# STM32F407.net
KiCad netlist of a schematic drawn in Altium Designer
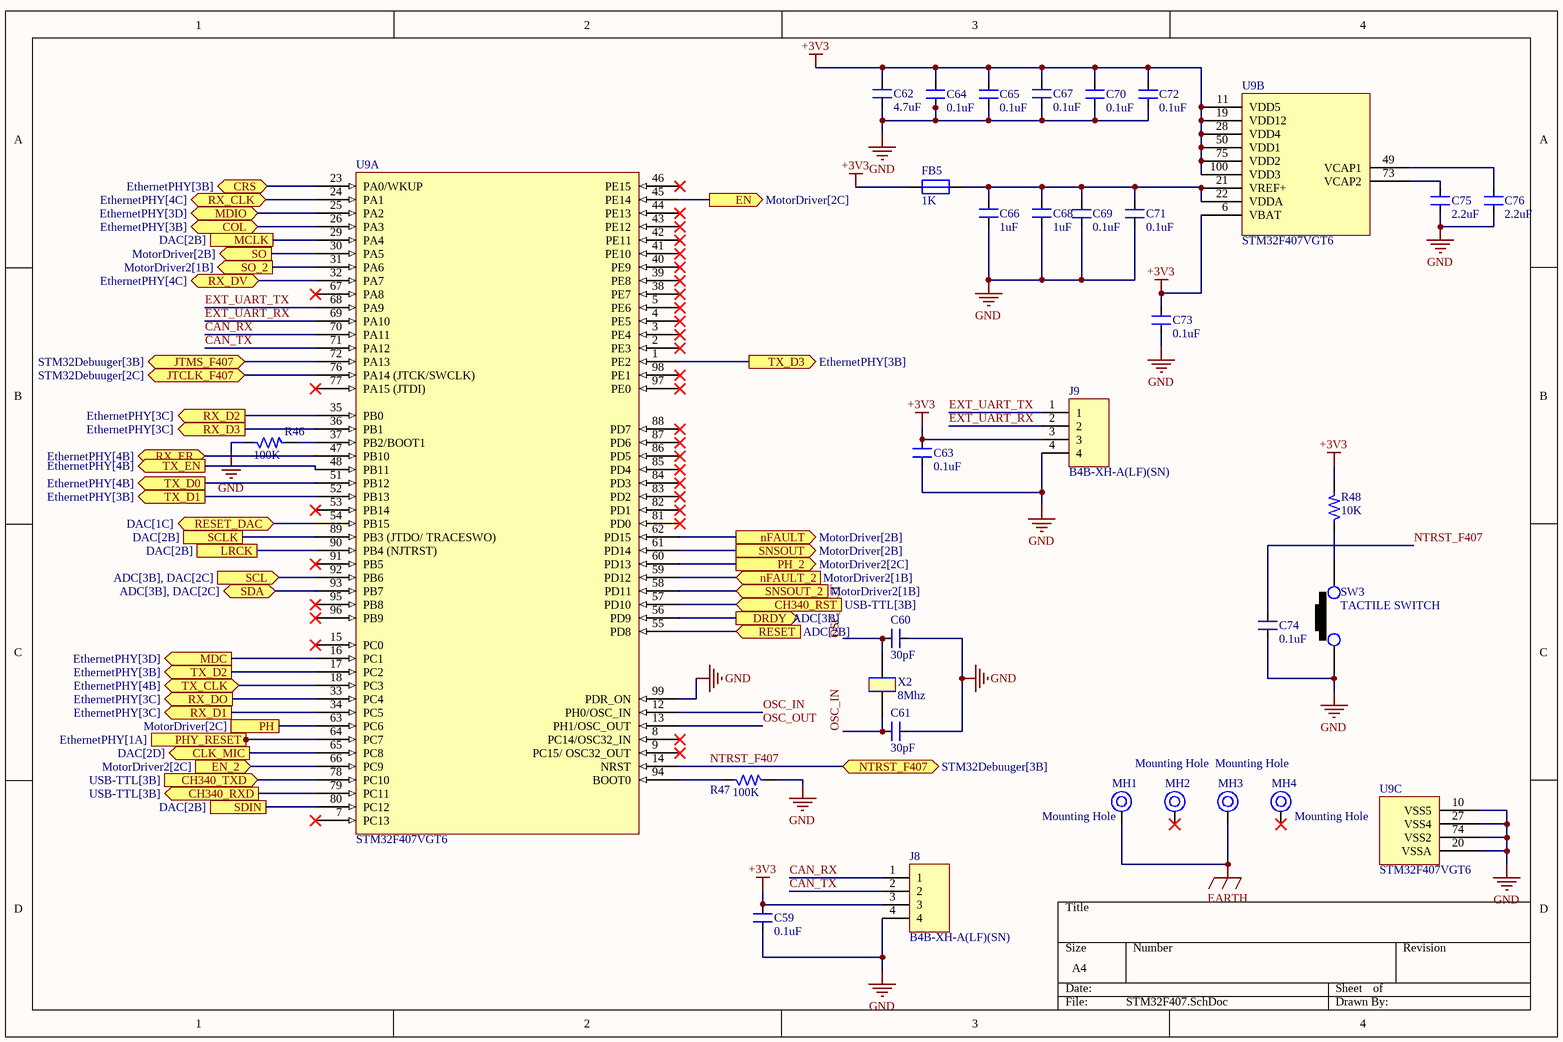
[diagram p0: STM32F407.SchDoc]

(export (version "E")
  (design (tool "Eeschema 10.0.6"))
  (components
    (comp (ref "C59")
      (value "0.1uF")
      (footprint "CAP_0805")
      (description "0.1µF ±10% 50V Ceramic Capacitor X7R 0805 (2012 Metric)")
      (fields
        (field (name "MANUFACTURER") "Samsung")
        (field (name "MANUFACTURER PART NUMBER") "CL21B104KBCNNNC")
      )
      (libsource (lib "ESTEEMPCBLIB") (part "CAP_0.1uF-50V-10%-0805"))
    )
    (comp (ref "C60")
      (value "30pF")
      (footprint "CAP_0805")
      (description "±10% 50V Ceramic Capacitor C0G, NP0 0805 (2012 Metric)")
      (fields
        (field (name "MANUFACTURER PART NUMBER") "C0805C300K5GAC7800")
        (field (name "MANUFACTURER") "KEMET")
      )
      (libsource (lib "ESTEEMPCBLIB") (part "CAP_30pF-50V-10%-0805"))
    )
    (comp (ref "C61")
      (value "30pF")
      (footprint "CAP_0805")
      (description "±10% 50V Ceramic Capacitor C0G, NP0 0805 (2012 Metric)")
      (fields
        (field (name "MANUFACTURER PART NUMBER") "C0805C300K5GAC7800")
        (field (name "MANUFACTURER") "KEMET")
      )
      (libsource (lib "ESTEEMPCBLIB") (part "CAP_30pF-50V-10%-0805"))
    )
    (comp (ref "C62")
      (value "4.7uF")
      (footprint "CAP_0805")
      (description "4.7µF ±10% 50V Ceramic Capacitor X5R 0805 (2012 Metric)")
      (fields
        (field (name "MANUFACTURER") "Yageo")
        (field (name "MANUFACTURER PART NUMBER") "GRM21BR61H475KE51L")
      )
      (libsource (lib "ESTEEMPCBLIB") (part "CAP_4.7uF-50V-10%-0805"))
    )
    (comp (ref "C63")
      (value "0.1uF")
      (footprint "CAP_0805")
      (description "0.1µF ±10% 50V Ceramic Capacitor X7R 0805 (2012 Metric)")
      (fields
        (field (name "MANUFACTURER") "Samsung")
        (field (name "MANUFACTURER PART NUMBER") "CL21B104KBCNNNC")
      )
      (libsource (lib "ESTEEMPCBLIB") (part "CAP_0.1uF-50V-10%-0805"))
    )
    (comp (ref "C64")
      (value "0.1uF")
      (footprint "CAP_0805")
      (description "0.1µF ±10% 50V Ceramic Capacitor X7R 0805 (2012 Metric)")
      (fields
        (field (name "MANUFACTURER") "Samsung")
        (field (name "MANUFACTURER PART NUMBER") "CL21B104KBCNNNC")
      )
      (libsource (lib "ESTEEMPCBLIB") (part "CAP_0.1uF-50V-10%-0805"))
    )
    (comp (ref "C65")
      (value "0.1uF")
      (footprint "CAP_0805")
      (description "0.1µF ±10% 50V Ceramic Capacitor X7R 0805 (2012 Metric)")
      (fields
        (field (name "MANUFACTURER") "Samsung")
        (field (name "MANUFACTURER PART NUMBER") "CL21B104KBCNNNC")
      )
      (libsource (lib "ESTEEMPCBLIB") (part "CAP_0.1uF-50V-10%-0805"))
    )
    (comp (ref "C66")
      (value "1uF")
      (footprint "CAP_0805")
      (description "1µF ±5% 50V Ceramic Capacitor X7R 0805 (2012 Metric)")
      (fields
        (field (name "MANUFACTURER") "Samsung")
        (field (name "MANUFACTURER PART NUMBER") "CC0805JKX7R9BB105")
      )
      (libsource (lib "ESTEEMPCBLIB") (part "CAP_1uF-50V-5%-0805"))
    )
    (comp (ref "C67")
      (value "0.1uF")
      (footprint "CAP_0805")
      (description "0.1µF ±10% 50V Ceramic Capacitor X7R 0805 (2012 Metric)")
      (fields
        (field (name "MANUFACTURER") "Samsung")
        (field (name "MANUFACTURER PART NUMBER") "CL21B104KBCNNNC")
      )
      (libsource (lib "ESTEEMPCBLIB") (part "CAP_0.1uF-50V-10%-0805"))
    )
    (comp (ref "C68")
      (value "1uF")
      (footprint "CAP_0805")
      (description "1µF ±5% 50V Ceramic Capacitor X7R 0805 (2012 Metric)")
      (fields
        (field (name "MANUFACTURER") "Samsung")
        (field (name "MANUFACTURER PART NUMBER") "CC0805JKX7R9BB105")
      )
      (libsource (lib "ESTEEMPCBLIB") (part "CAP_1uF-50V-5%-0805"))
    )
    (comp (ref "C69")
      (value "0.1uF")
      (footprint "CAP_0805")
      (description "0.1µF ±10% 50V Ceramic Capacitor X7R 0805 (2012 Metric)")
      (fields
        (field (name "MANUFACTURER") "Samsung")
        (field (name "MANUFACTURER PART NUMBER") "CL21B104KBCNNNC")
      )
      (libsource (lib "ESTEEMPCBLIB") (part "CAP_0.1uF-50V-10%-0805"))
    )
    (comp (ref "C70")
      (value "0.1uF")
      (footprint "CAP_0805")
      (description "0.1µF ±10% 50V Ceramic Capacitor X7R 0805 (2012 Metric)")
      (fields
        (field (name "MANUFACTURER") "Samsung")
        (field (name "MANUFACTURER PART NUMBER") "CL21B104KBCNNNC")
      )
      (libsource (lib "ESTEEMPCBLIB") (part "CAP_0.1uF-50V-10%-0805"))
    )
    (comp (ref "C71")
      (value "0.1uF")
      (footprint "CAP_0805")
      (description "0.1µF ±10% 50V Ceramic Capacitor X7R 0805 (2012 Metric)")
      (fields
        (field (name "MANUFACTURER") "Samsung")
        (field (name "MANUFACTURER PART NUMBER") "CL21B104KBCNNNC")
      )
      (libsource (lib "ESTEEMPCBLIB") (part "CAP_0.1uF-50V-10%-0805"))
    )
    (comp (ref "C72")
      (value "0.1uF")
      (footprint "CAP_0805")
      (description "0.1µF ±10% 50V Ceramic Capacitor X7R 0805 (2012 Metric)")
      (fields
        (field (name "MANUFACTURER") "Samsung")
        (field (name "MANUFACTURER PART NUMBER") "CL21B104KBCNNNC")
      )
      (libsource (lib "ESTEEMPCBLIB") (part "CAP_0.1uF-50V-10%-0805"))
    )
    (comp (ref "C73")
      (value "0.1uF")
      (footprint "CAP_0805")
      (description "0.1µF ±10% 50V Ceramic Capacitor X7R 0805 (2012 Metric)")
      (fields
        (field (name "MANUFACTURER") "Samsung")
        (field (name "MANUFACTURER PART NUMBER") "CL21B104KBCNNNC")
      )
      (libsource (lib "ESTEEMPCBLIB") (part "CAP_0.1uF-50V-10%-0805"))
    )
    (comp (ref "C74")
      (value "0.1uF")
      (footprint "CAP_0805")
      (description "0.1µF ±10% 50V Ceramic Capacitor X7R 0805 (2012 Metric)")
      (fields
        (field (name "MANUFACTURER") "Samsung")
        (field (name "MANUFACTURER PART NUMBER") "CL21B104KBCNNNC")
      )
      (libsource (lib "ESTEEMPCBLIB") (part "CAP_0.1uF-50V-10%-0805"))
    )
    (comp (ref "C75")
      (value "2.2uF")
      (footprint "CAP_0805")
      (description "2.2µF ±10% 25V Ceramic Capacitor X7R 0805 (2012 Metric)")
      (fields
        (field (name "MANUFACTURER") "KEMET")
        (field (name "MANUFACTURER PART NUMBER") "CL21B225KAFNFNE")
      )
      (libsource (lib "ESTEEMPCBLIB") (part "CAP_2.2uF-25V-10%-0805"))
    )
    (comp (ref "C76")
      (value "2.2uF")
      (footprint "CAP_0805")
      (description "2.2µF ±10% 25V Ceramic Capacitor X7R 0805 (2012 Metric)")
      (fields
        (field (name "MANUFACTURER") "KEMET")
        (field (name "MANUFACTURER PART NUMBER") "CL21B225KAFNFNE")
      )
      (libsource (lib "ESTEEMPCBLIB") (part "CAP_2.2uF-25V-10%-0805"))
    )
    (comp (ref "FB5")
      (value "1K")
      (footprint "IND_0805")
      (description "1 kOhms @ 100MHz 1 Power Line Ferrite Bead 0805 (2012 Metric) 1.6A")
      (fields
        (field (name "MANUFACTURER") "Laird")
        (field (name "MANUFACTURER PART NUMBER") "BLM21SP102SH1D")
      )
      (libsource (lib "ESTEEMPCBLIB") (part "FB_1K-100MHZ-1.6A-0805"))
    )
    (comp (ref "J8")
      (value "B4B-XH-A(LF)(SN)")
      (footprint "CON4_100_B4B-XH-A_TH_ST")
      (description "4 Pins, 1 Row 2.54mm Pitch, straight Connector, male")
      (fields (field (name "MANUFACTURER") "Wurth Electronics") (field (name "MATING PART NUMBER") "XHP-4"))
      (libsource (lib "ESTEEMPCBLIB") (part "CON-PLG_4X1-100-ST-TH"))
    )
    (comp (ref "J9")
      (value "B4B-XH-A(LF)(SN)")
      (footprint "CON4_100_B4B-XH-A_TH_ST")
      (description "4 Pins, 1 Row 2.54mm Pitch, straight Connector, male")
      (fields (field (name "MANUFACTURER") "Wurth Electronics") (field (name "MATING PART NUMBER") "XHP-4"))
      (libsource (lib "ESTEEMPCBLIB") (part "CON-PLG_4X1-100-ST-TH"))
    )
    (comp (ref "MH1")
      (value "Mounting Hole")
      (footprint "MOUNTING")
      (fields (field (name "MANUFACTURER PART NUMBER") "NA"))
      (libsource (lib "ESTEEMPCBLIB") (part "MH_3.5H_6D"))
    )
    (comp (ref "MH2")
      (value "Mounting Hole")
      (footprint "MOUNTING")
      (fields (field (name "MANUFACTURER PART NUMBER") "NA"))
      (libsource (lib "ESTEEMPCBLIB") (part "MH_3.5H_6D"))
    )
    (comp (ref "MH3")
      (value "Mounting Hole")
      (footprint "MOUNTING")
      (fields (field (name "MANUFACTURER PART NUMBER") "NA"))
      (libsource (lib "ESTEEMPCBLIB") (part "MH_3.5H_6D"))
    )
    (comp (ref "MH4")
      (value "Mounting Hole")
      (footprint "MOUNTING")
      (fields (field (name "MANUFACTURER PART NUMBER") "NA"))
      (libsource (lib "ESTEEMPCBLIB") (part "MH_3.5H_6D"))
    )
    (comp (ref "R46")
      (value "100K")
      (footprint "RES_0603")
      (description "100 kOhms ±1% 0.1W, 1/10W Chip Resistor 0603 (1608 Metric) Automotive AEC-Q200 Thick Film")
      (fields
        (field (name "MANUFACTURER") "Stackpole Electronics")
        (field (name "MANUFACTURER PART NUMBER") "RMCF0603FT100K")
      )
      (libsource (lib "ESTEEMPCBLIB") (part "RES_100K-0.1W-1%-0603"))
    )
    (comp (ref "R47")
      (value "100K")
      (footprint "RES_0603")
      (description "100 kOhms ±1% 0.1W, 1/10W Chip Resistor 0603 (1608 Metric) Automotive AEC-Q200 Thick Film")
      (fields
        (field (name "MANUFACTURER") "Stackpole Electronics")
        (field (name "MANUFACTURER PART NUMBER") "RMCF0603FT100K")
      )
      (libsource (lib "ESTEEMPCBLIB") (part "RES_100K-0.1W-1%-0603"))
    )
    (comp (ref "R48")
      (value "10K")
      (footprint "RES_0603")
      (description "10 kOhms ±1% 0.1W, 1/10W Chip Resistor 0603 (1608 Metric) Automotive AEC-Q200 Thick Film")
      (fields (field (name "MANUFACTURER") "Walsin") (field (name "MANUFACTURER PART NUMBER") "WR06X1002FTL"))
      (libsource (lib "ESTEEMPCBLIB") (part "RES_10K-0.1W-1%-0603"))
    )
    (comp (ref "SW3")
      (value "TACTILE SWITCH")
      (footprint "SW_342_SMD")
      (description "Tactile Switch SPST-NO Top Actuated Surface Mount")
      (fields
        (field (name "MANUFACTURER") "ITT C&K")
        (field (name "MANUFACTURER PART NUMBER") "RS-282G05A3-SMRT")
      )
      (libsource (lib "ESTEEMPCBLIB") (part "SW1_RS-282G05A3-SMRT-SMD"))
    )
    (comp (ref "U9")
      (value "STM32F407VGT6")
      (footprint "QFN100_19.6_669_58X10_SMD")
      (description "ARM® Cortex®-M4 STM32F4 Microcontroller IC 32-Bit 168MHz 1MB (1M x 8) FLASH 100-LQFP (14x14)")
      (fields (field (name "MANUFACTURER") "STMicroelectronics"))
      (libsource (lib "ESTEEMPCBLIB") (part "IC_STM32F407VGT6"))
    )
    (comp (ref "X2")
      (value "8Mhz")
      (footprint "XTAL_314_240X47_SMD")
      (description "8MHz ±30ppm Crystal 32pF 60 Ohms HC-49/US")
      (fields
        (field (name "MANUFACTURER") "Fox Electronics")
        (field (name "MANUFACTURER PART NUMBER") "ECS-80-32-5PX-TR")
      )
      (libsource (lib "ESTEEMPCBLIB") (part "XTAL_8MHZ-ECS-80-32-5PX-SMD"))
    )
  )
  (nets
    (net (code "1") (name "+3V3") (class "Default")
      (node (ref "C59") (pin "2") (pinfunction "2_2") (pintype "passive"))
      (node (ref "C62") (pin "2") (pinfunction "2_2") (pintype "passive"))
      (node (ref "C63") (pin "2") (pinfunction "2_2") (pintype "passive"))
      (node (ref "C64") (pin "2") (pinfunction "2_2") (pintype "passive"))
      (node (ref "C65") (pin "2") (pinfunction "2_2") (pintype "passive"))
      (node (ref "C67") (pin "2") (pinfunction "2_2") (pintype "passive"))
      (node (ref "C70") (pin "2") (pinfunction "2_2") (pintype "passive"))
      (node (ref "C72") (pin "2") (pinfunction "2_2") (pintype "passive"))
      (node (ref "C73") (pin "2") (pinfunction "2_2") (pintype "passive"))
      (node (ref "FB5") (pin "1") (pinfunction "1_1") (pintype "passive"))
      (node (ref "J8") (pin "3") (pinfunction "3_3") (pintype "passive"))
      (node (ref "J9") (pin "3") (pinfunction "3_3") (pintype "passive"))
      (node (ref "R48") (pin "2") (pinfunction "2_2") (pintype "passive"))
      (node (ref "U9") (pin "100") (pinfunction "VDD3_100") (pintype "passive"))
      (node (ref "U9") (pin "11") (pinfunction "VDD5_11") (pintype "passive"))
      (node (ref "U9") (pin "19") (pinfunction "VDD12_19") (pintype "passive"))
      (node (ref "U9") (pin "28") (pinfunction "VDD4_28") (pintype "passive"))
      (node (ref "U9") (pin "50") (pinfunction "VDD1_50") (pintype "passive"))
      (node (ref "U9") (pin "6") (pinfunction "VBAT_6") (pintype "passive"))
      (node (ref "U9") (pin "75") (pinfunction "VDD2_75") (pintype "passive"))
    )
    (net (code "2") (name "/CAN_RX") (class "Default")
      (node (ref "J8") (pin "1") (pinfunction "1_1") (pintype "passive"))
      (node (ref "U9") (pin "70") (pinfunction "PA11_70") (pintype "input"))
    )
    (net (code "3") (name "/CAN_TX") (class "Default")
      (node (ref "J8") (pin "2") (pinfunction "2_2") (pintype "passive"))
      (node (ref "U9") (pin "71") (pinfunction "PA12_71") (pintype "input"))
    )
    (net (code "4") (name "/CH340_RST") (class "Default")
      (node (ref "U9") (pin "57") (pinfunction "PD10_57") (pintype "input"))
    )
    (net (code "5") (name "/CH340_RXD") (class "Default")
      (node (ref "U9") (pin "79") (pinfunction "PC11_79") (pintype "input"))
    )
    (net (code "6") (name "/CH340_TXD") (class "Default")
      (node (ref "U9") (pin "78") (pinfunction "PC10_78") (pintype "input"))
    )
    (net (code "7") (name "/CLK_MIC") (class "Default")
      (node (ref "U9") (pin "65") (pinfunction "PC8_65") (pintype "input"))
    )
    (net (code "8") (name "/COL") (class "Default")
      (node (ref "U9") (pin "26") (pinfunction "PA3_26") (pintype "input"))
    )
    (net (code "9") (name "/CRS") (class "Default")
      (node (ref "U9") (pin "23") (pinfunction "PA0/WKUP_23") (pintype "input"))
    )
    (net (code "10") (name "/DRDY") (class "Default")
      (node (ref "U9") (pin "56") (pinfunction "PD9_56") (pintype "input"))
    )
    (net (code "11") (name "/EN") (class "Default")
      (node (ref "U9") (pin "45") (pinfunction "PE14_45") (pintype "input"))
    )
    (net (code "12") (name "/EN_2") (class "Default")
      (node (ref "U9") (pin "66") (pinfunction "PC9_66") (pintype "input"))
    )
    (net (code "13") (name "/EXT_UART_RX") (class "Default")
      (node (ref "J9") (pin "2") (pinfunction "2_2") (pintype "passive"))
      (node (ref "U9") (pin "69") (pinfunction "PA10_69") (pintype "input"))
    )
    (net (code "14") (name "/EXT_UART_TX") (class "Default")
      (node (ref "J9") (pin "1") (pinfunction "1_1") (pintype "passive"))
      (node (ref "U9") (pin "68") (pinfunction "PA9_68") (pintype "input"))
    )
    (net (code "15") (name "/JTCLK_F407") (class "Default")
      (node (ref "U9") (pin "76") (pinfunction "PA14_(JTCK/SWCLK)_76") (pintype "input"))
    )
    (net (code "16") (name "/JTMS_F407") (class "Default")
      (node (ref "U9") (pin "72") (pinfunction "PA13_72") (pintype "input"))
    )
    (net (code "17") (name "/LRCK") (class "Default")
      (node (ref "U9") (pin "90") (pinfunction "PB4_(NJTRST)_90") (pintype "input"))
    )
    (net (code "18") (name "/MCLK") (class "Default")
      (node (ref "U9") (pin "29") (pinfunction "PA4_29") (pintype "input"))
    )
    (net (code "19") (name "/MDC") (class "Default")
      (node (ref "U9") (pin "16") (pinfunction "PC1_16") (pintype "input"))
    )
    (net (code "20") (name "/MDIO") (class "Default")
      (node (ref "U9") (pin "25") (pinfunction "PA2_25") (pintype "input"))
    )
    (net (code "21") (name "/NTRST_F407") (class "Default")
      (node (ref "C74") (pin "2") (pinfunction "2_2") (pintype "passive"))
      (node (ref "U9") (pin "14") (pinfunction "NRST_14") (pintype "input"))
    )
    (net (code "22") (name "/OSC_IN") (class "Default")
      (node (ref "C61") (pin "1") (pinfunction "1_1") (pintype "passive"))
      (node (ref "U9") (pin "12") (pinfunction "PH0/OSC_IN_12") (pintype "input"))
      (node (ref "X2") (pin "1") (pinfunction "1_1") (pintype "passive"))
    )
    (net (code "23") (name "/OSC_OUT") (class "Default")
      (node (ref "C60") (pin "1") (pinfunction "1_1") (pintype "passive"))
      (node (ref "U9") (pin "13") (pinfunction "PH1/OSC_OUT_13") (pintype "input"))
      (node (ref "X2") (pin "2") (pinfunction "2_2") (pintype "passive"))
    )
    (net (code "24") (name "/PH") (class "Default")
      (node (ref "U9") (pin "63") (pinfunction "PC6_63") (pintype "input"))
    )
    (net (code "25") (name "/PHY_RESET") (class "Default")
      (node (ref "U9") (pin "64") (pinfunction "PC7_64") (pintype "input"))
    )
    (net (code "26") (name "/PH_2") (class "Default")
      (node (ref "U9") (pin "60") (pinfunction "PD13_60") (pintype "input"))
    )
    (net (code "27") (name "/RESET") (class "Default")
      (node (ref "U9") (pin "55") (pinfunction "PD8_55") (pintype "input"))
    )
    (net (code "28") (name "/RESET_DAC") (class "Default")
      (node (ref "U9") (pin "54") (pinfunction "PB15_54") (pintype "input"))
    )
    (net (code "29") (name "/RX_CLK") (class "Default")
      (node (ref "U9") (pin "24") (pinfunction "PA1_24") (pintype "input"))
    )
    (net (code "30") (name "/RX_D1") (class "Default")
      (node (ref "U9") (pin "34") (pinfunction "PC5_34") (pintype "input"))
    )
    (net (code "31") (name "/RX_D2") (class "Default")
      (node (ref "U9") (pin "35") (pinfunction "PB0_35") (pintype "input"))
    )
    (net (code "32") (name "/RX_D3") (class "Default")
      (node (ref "U9") (pin "36") (pinfunction "PB1_36") (pintype "input"))
    )
    (net (code "33") (name "/RX_DO") (class "Default")
      (node (ref "U9") (pin "33") (pinfunction "PC4_33") (pintype "input"))
    )
    (net (code "34") (name "/RX_DV") (class "Default")
      (node (ref "U9") (pin "32") (pinfunction "PA7_32") (pintype "input"))
    )
    (net (code "35") (name "/RX_ER") (class "Default")
      (node (ref "U9") (pin "47") (pinfunction "PB10_47") (pintype "input"))
    )
    (net (code "36") (name "/SCL") (class "Default")
      (node (ref "U9") (pin "92") (pinfunction "PB6_92") (pintype "input"))
    )
    (net (code "37") (name "/SCLK") (class "Default")
      (node (ref "U9") (pin "89") (pinfunction "PB3_(JTDO/_TRACESWO)_89") (pintype "input"))
    )
    (net (code "38") (name "/SDA") (class "Default")
      (node (ref "U9") (pin "93") (pinfunction "PB7_93") (pintype "input"))
    )
    (net (code "39") (name "/SDIN") (class "Default")
      (node (ref "U9") (pin "80") (pinfunction "PC12_80") (pintype "input"))
    )
    (net (code "40") (name "/SNSOUT") (class "Default")
      (node (ref "U9") (pin "61") (pinfunction "PD14_61") (pintype "input"))
    )
    (net (code "41") (name "/SNSOUT_2") (class "Default")
      (node (ref "U9") (pin "58") (pinfunction "PD11_58") (pintype "input"))
    )
    (net (code "42") (name "/SO") (class "Default")
      (node (ref "U9") (pin "30") (pinfunction "PA5_30") (pintype "input"))
    )
    (net (code "43") (name "/SO_2") (class "Default")
      (node (ref "U9") (pin "31") (pinfunction "PA6_31") (pintype "input"))
    )
    (net (code "44") (name "/TX_CLK") (class "Default")
      (node (ref "U9") (pin "18") (pinfunction "PC3_18") (pintype "input"))
    )
    (net (code "45") (name "/TX_D0") (class "Default")
      (node (ref "U9") (pin "51") (pinfunction "PB12_51") (pintype "input"))
    )
    (net (code "46") (name "/TX_D1") (class "Default")
      (node (ref "U9") (pin "52") (pinfunction "PB13_52") (pintype "input"))
    )
    (net (code "47") (name "/TX_D2") (class "Default")
      (node (ref "U9") (pin "17") (pinfunction "PC2_17") (pintype "input"))
    )
    (net (code "48") (name "/TX_D3") (class "Default")
      (node (ref "U9") (pin "1") (pinfunction "PE2_1") (pintype "input"))
    )
    (net (code "49") (name "/TX_EN") (class "Default")
      (node (ref "U9") (pin "48") (pinfunction "PB11_48") (pintype "input"))
    )
    (net (code "50") (name "/nFAULT") (class "Default")
      (node (ref "U9") (pin "62") (pinfunction "PD15_62") (pintype "input"))
    )
    (net (code "51") (name "/nFAULT_2") (class "Default")
      (node (ref "U9") (pin "59") (pinfunction "PD12_59") (pintype "input"))
    )
    (net (code "52") (name "EARTH") (class "Default")
      (node (ref "MH1") (pin "1") (pinfunction "1_1") (pintype "passive"))
      (node (ref "MH3") (pin "1") (pinfunction "1_1") (pintype "passive"))
    )
    (net (code "53") (name "GND") (class "Default")
      (node (ref "C59") (pin "1") (pinfunction "1_1") (pintype "passive"))
      (node (ref "C60") (pin "2") (pinfunction "2_2") (pintype "passive"))
      (node (ref "C61") (pin "2") (pinfunction "2_2") (pintype "passive"))
      (node (ref "C62") (pin "1") (pinfunction "1_1") (pintype "passive"))
      (node (ref "C63") (pin "1") (pinfunction "1_1") (pintype "passive"))
      (node (ref "C64") (pin "1") (pinfunction "1_1") (pintype "passive"))
      (node (ref "C65") (pin "1") (pinfunction "1_1") (pintype "passive"))
      (node (ref "C66") (pin "1") (pinfunction "1_1") (pintype "passive"))
      (node (ref "C67") (pin "1") (pinfunction "1_1") (pintype "passive"))
      (node (ref "C68") (pin "1") (pinfunction "1_1") (pintype "passive"))
      (node (ref "C69") (pin "1") (pinfunction "1_1") (pintype "passive"))
      (node (ref "C70") (pin "1") (pinfunction "1_1") (pintype "passive"))
      (node (ref "C71") (pin "1") (pinfunction "1_1") (pintype "passive"))
      (node (ref "C72") (pin "1") (pinfunction "1_1") (pintype "passive"))
      (node (ref "C73") (pin "1") (pinfunction "1_1") (pintype "passive"))
      (node (ref "C74") (pin "1") (pinfunction "1_1") (pintype "passive"))
      (node (ref "C75") (pin "1") (pinfunction "1_1") (pintype "passive"))
      (node (ref "C76") (pin "1") (pinfunction "1_1") (pintype "passive"))
      (node (ref "J8") (pin "4") (pinfunction "4_4") (pintype "passive"))
      (node (ref "J9") (pin "4") (pinfunction "4_4") (pintype "passive"))
      (node (ref "R46") (pin "1") (pinfunction "1_1") (pintype "passive"))
      (node (ref "R47") (pin "2") (pinfunction "2_2") (pintype "passive"))
      (node (ref "SW3") (pin "1") (pinfunction "1_1") (pintype "passive"))
      (node (ref "U9") (pin "10") (pinfunction "VSS5_10") (pintype "passive"))
      (node (ref "U9") (pin "20") (pinfunction "VSSA_20") (pintype "passive"))
      (node (ref "U9") (pin "27") (pinfunction "VSS4_27") (pintype "passive"))
      (node (ref "U9") (pin "74") (pinfunction "VSS2_74") (pintype "passive"))
      (node (ref "U9") (pin "99") (pinfunction "PDR_ON_99") (pintype "input"))
    )
    (net (code "54") (name "Net-(R48-Pad1)") (class "Default")
      (node (ref "R48") (pin "1") (pinfunction "1_1") (pintype "passive"))
      (node (ref "SW3") (pin "2") (pinfunction "2_2") (pintype "passive"))
    )
    (net (code "55") (name "Net-(U9A-BOOT0)") (class "Default")
      (node (ref "R47") (pin "1") (pinfunction "1_1") (pintype "passive"))
      (node (ref "U9") (pin "94") (pinfunction "BOOT0_94") (pintype "input"))
    )
    (net (code "56") (name "Net-(U9A-PB2{slash}BOOT1)") (class "Default")
      (node (ref "R46") (pin "2") (pinfunction "2_2") (pintype "passive"))
      (node (ref "U9") (pin "37") (pinfunction "PB2/BOOT1_37") (pintype "input"))
    )
    (net (code "57") (name "Net-(U9B-VCAP1)") (class "Default")
      (node (ref "C76") (pin "2") (pinfunction "2_2") (pintype "passive"))
      (node (ref "U9") (pin "49") (pinfunction "VCAP1_49") (pintype "passive"))
    )
    (net (code "58") (name "Net-(U9B-VCAP2)") (class "Default")
      (node (ref "C75") (pin "2") (pinfunction "2_2") (pintype "passive"))
      (node (ref "U9") (pin "73") (pinfunction "VCAP2_73") (pintype "passive"))
    )
    (net (code "59") (name "Net-(U9B-VDDA)") (class "Default")
      (node (ref "C66") (pin "2") (pinfunction "2_2") (pintype "passive"))
      (node (ref "C68") (pin "2") (pinfunction "2_2") (pintype "passive"))
      (node (ref "C69") (pin "2") (pinfunction "2_2") (pintype "passive"))
      (node (ref "C71") (pin "2") (pinfunction "2_2") (pintype "passive"))
      (node (ref "FB5") (pin "2") (pinfunction "2_2") (pintype "passive"))
      (node (ref "U9") (pin "21") (pinfunction "VREF+_21") (pintype "passive"))
      (node (ref "U9") (pin "22") (pinfunction "VDDA_22") (pintype "passive"))
    )
    (net (code "60") (name "unconnected-(MH2-Pad1)") (class "Default")
      (node (ref "MH2") (pin "1") (pinfunction "1_1") (pintype "passive+no_connect"))
    )
    (net (code "61") (name "unconnected-(MH4-Pad1)") (class "Default")
      (node (ref "MH4") (pin "1") (pinfunction "1_1") (pintype "passive+no_connect"))
    )
    (net (code "62") (name "unconnected-(U9A-PA8-Pad67)") (class "Default")
      (node (ref "U9") (pin "67") (pinfunction "PA8_67") (pintype "input+no_connect"))
    )
    (net (code "63") (name "unconnected-(U9A-PA15_(JTDI)-Pad77)") (class "Default")
      (node (ref "U9") (pin "77") (pinfunction "PA15_(JTDI)_77") (pintype "input+no_connect"))
    )
    (net (code "64") (name "unconnected-(U9A-PB5-Pad91)") (class "Default")
      (node (ref "U9") (pin "91") (pinfunction "PB5_91") (pintype "input+no_connect"))
    )
    (net (code "65") (name "unconnected-(U9A-PB8-Pad95)") (class "Default")
      (node (ref "U9") (pin "95") (pinfunction "PB8_95") (pintype "input+no_connect"))
    )
    (net (code "66") (name "unconnected-(U9A-PB9-Pad96)") (class "Default")
      (node (ref "U9") (pin "96") (pinfunction "PB9_96") (pintype "input+no_connect"))
    )
    (net (code "67") (name "unconnected-(U9A-PB14-Pad53)") (class "Default")
      (node (ref "U9") (pin "53") (pinfunction "PB14_53") (pintype "input+no_connect"))
    )
    (net (code "68") (name "unconnected-(U9A-PC0-Pad15)") (class "Default")
      (node (ref "U9") (pin "15") (pinfunction "PC0_15") (pintype "input+no_connect"))
    )
    (net (code "69") (name "unconnected-(U9A-PC13-Pad7)") (class "Default")
      (node (ref "U9") (pin "7") (pinfunction "PC13_7") (pintype "input+no_connect"))
    )
    (net (code "70") (name "unconnected-(U9A-PC14{slash}OSC32_IN-Pad8)") (class "Default")
      (node (ref "U9") (pin "8") (pinfunction "PC14/OSC32_IN_8") (pintype "input+no_connect"))
    )
    (net (code "71") (name "unconnected-(U9A-PC15{slash}_OSC32_OUT-Pad9)") (class "Default")
      (node (ref "U9") (pin "9") (pinfunction "PC15/_OSC32_OUT_9") (pintype "input+no_connect"))
    )
    (net (code "72") (name "unconnected-(U9A-PD0-Pad81)") (class "Default")
      (node (ref "U9") (pin "81") (pinfunction "PD0_81") (pintype "input+no_connect"))
    )
    (net (code "73") (name "unconnected-(U9A-PD1-Pad82)") (class "Default")
      (node (ref "U9") (pin "82") (pinfunction "PD1_82") (pintype "input+no_connect"))
    )
    (net (code "74") (name "unconnected-(U9A-PD2-Pad83)") (class "Default")
      (node (ref "U9") (pin "83") (pinfunction "PD2_83") (pintype "input+no_connect"))
    )
    (net (code "75") (name "unconnected-(U9A-PD3-Pad84)") (class "Default")
      (node (ref "U9") (pin "84") (pinfunction "PD3_84") (pintype "input+no_connect"))
    )
    (net (code "76") (name "unconnected-(U9A-PD4-Pad85)") (class "Default")
      (node (ref "U9") (pin "85") (pinfunction "PD4_85") (pintype "input+no_connect"))
    )
    (net (code "77") (name "unconnected-(U9A-PD5-Pad86)") (class "Default")
      (node (ref "U9") (pin "86") (pinfunction "PD5_86") (pintype "input+no_connect"))
    )
    (net (code "78") (name "unconnected-(U9A-PD6-Pad87)") (class "Default")
      (node (ref "U9") (pin "87") (pinfunction "PD6_87") (pintype "input+no_connect"))
    )
    (net (code "79") (name "unconnected-(U9A-PD7-Pad88)") (class "Default")
      (node (ref "U9") (pin "88") (pinfunction "PD7_88") (pintype "input+no_connect"))
    )
    (net (code "80") (name "unconnected-(U9A-PE0-Pad97)") (class "Default")
      (node (ref "U9") (pin "97") (pinfunction "PE0_97") (pintype "input+no_connect"))
    )
    (net (code "81") (name "unconnected-(U9A-PE1-Pad98)") (class "Default")
      (node (ref "U9") (pin "98") (pinfunction "PE1_98") (pintype "input+no_connect"))
    )
    (net (code "82") (name "unconnected-(U9A-PE3-Pad2)") (class "Default")
      (node (ref "U9") (pin "2") (pinfunction "PE3_2") (pintype "input+no_connect"))
    )
    (net (code "83") (name "unconnected-(U9A-PE4-Pad3)") (class "Default")
      (node (ref "U9") (pin "3") (pinfunction "PE4_3") (pintype "input+no_connect"))
    )
    (net (code "84") (name "unconnected-(U9A-PE5-Pad4)") (class "Default")
      (node (ref "U9") (pin "4") (pinfunction "PE5_4") (pintype "input+no_connect"))
    )
    (net (code "85") (name "unconnected-(U9A-PE6-Pad5)") (class "Default")
      (node (ref "U9") (pin "5") (pinfunction "PE6_5") (pintype "input+no_connect"))
    )
    (net (code "86") (name "unconnected-(U9A-PE7-Pad38)") (class "Default")
      (node (ref "U9") (pin "38") (pinfunction "PE7_38") (pintype "input+no_connect"))
    )
    (net (code "87") (name "unconnected-(U9A-PE8-Pad39)") (class "Default")
      (node (ref "U9") (pin "39") (pinfunction "PE8_39") (pintype "input+no_connect"))
    )
    (net (code "88") (name "unconnected-(U9A-PE9-Pad40)") (class "Default")
      (node (ref "U9") (pin "40") (pinfunction "PE9_40") (pintype "input+no_connect"))
    )
    (net (code "89") (name "unconnected-(U9A-PE10-Pad41)") (class "Default")
      (node (ref "U9") (pin "41") (pinfunction "PE10_41") (pintype "input+no_connect"))
    )
    (net (code "90") (name "unconnected-(U9A-PE11-Pad42)") (class "Default")
      (node (ref "U9") (pin "42") (pinfunction "PE11_42") (pintype "input+no_connect"))
    )
    (net (code "91") (name "unconnected-(U9A-PE12-Pad43)") (class "Default")
      (node (ref "U9") (pin "43") (pinfunction "PE12_43") (pintype "input+no_connect"))
    )
    (net (code "92") (name "unconnected-(U9A-PE13-Pad44)") (class "Default")
      (node (ref "U9") (pin "44") (pinfunction "PE13_44") (pintype "input+no_connect"))
    )
    (net (code "93") (name "unconnected-(U9A-PE15-Pad46)") (class "Default")
      (node (ref "U9") (pin "46") (pinfunction "PE15_46") (pintype "input+no_connect"))
    )
  )
)
